# schematic.net
KiCad netlist of a schematic drawn in EAGLE
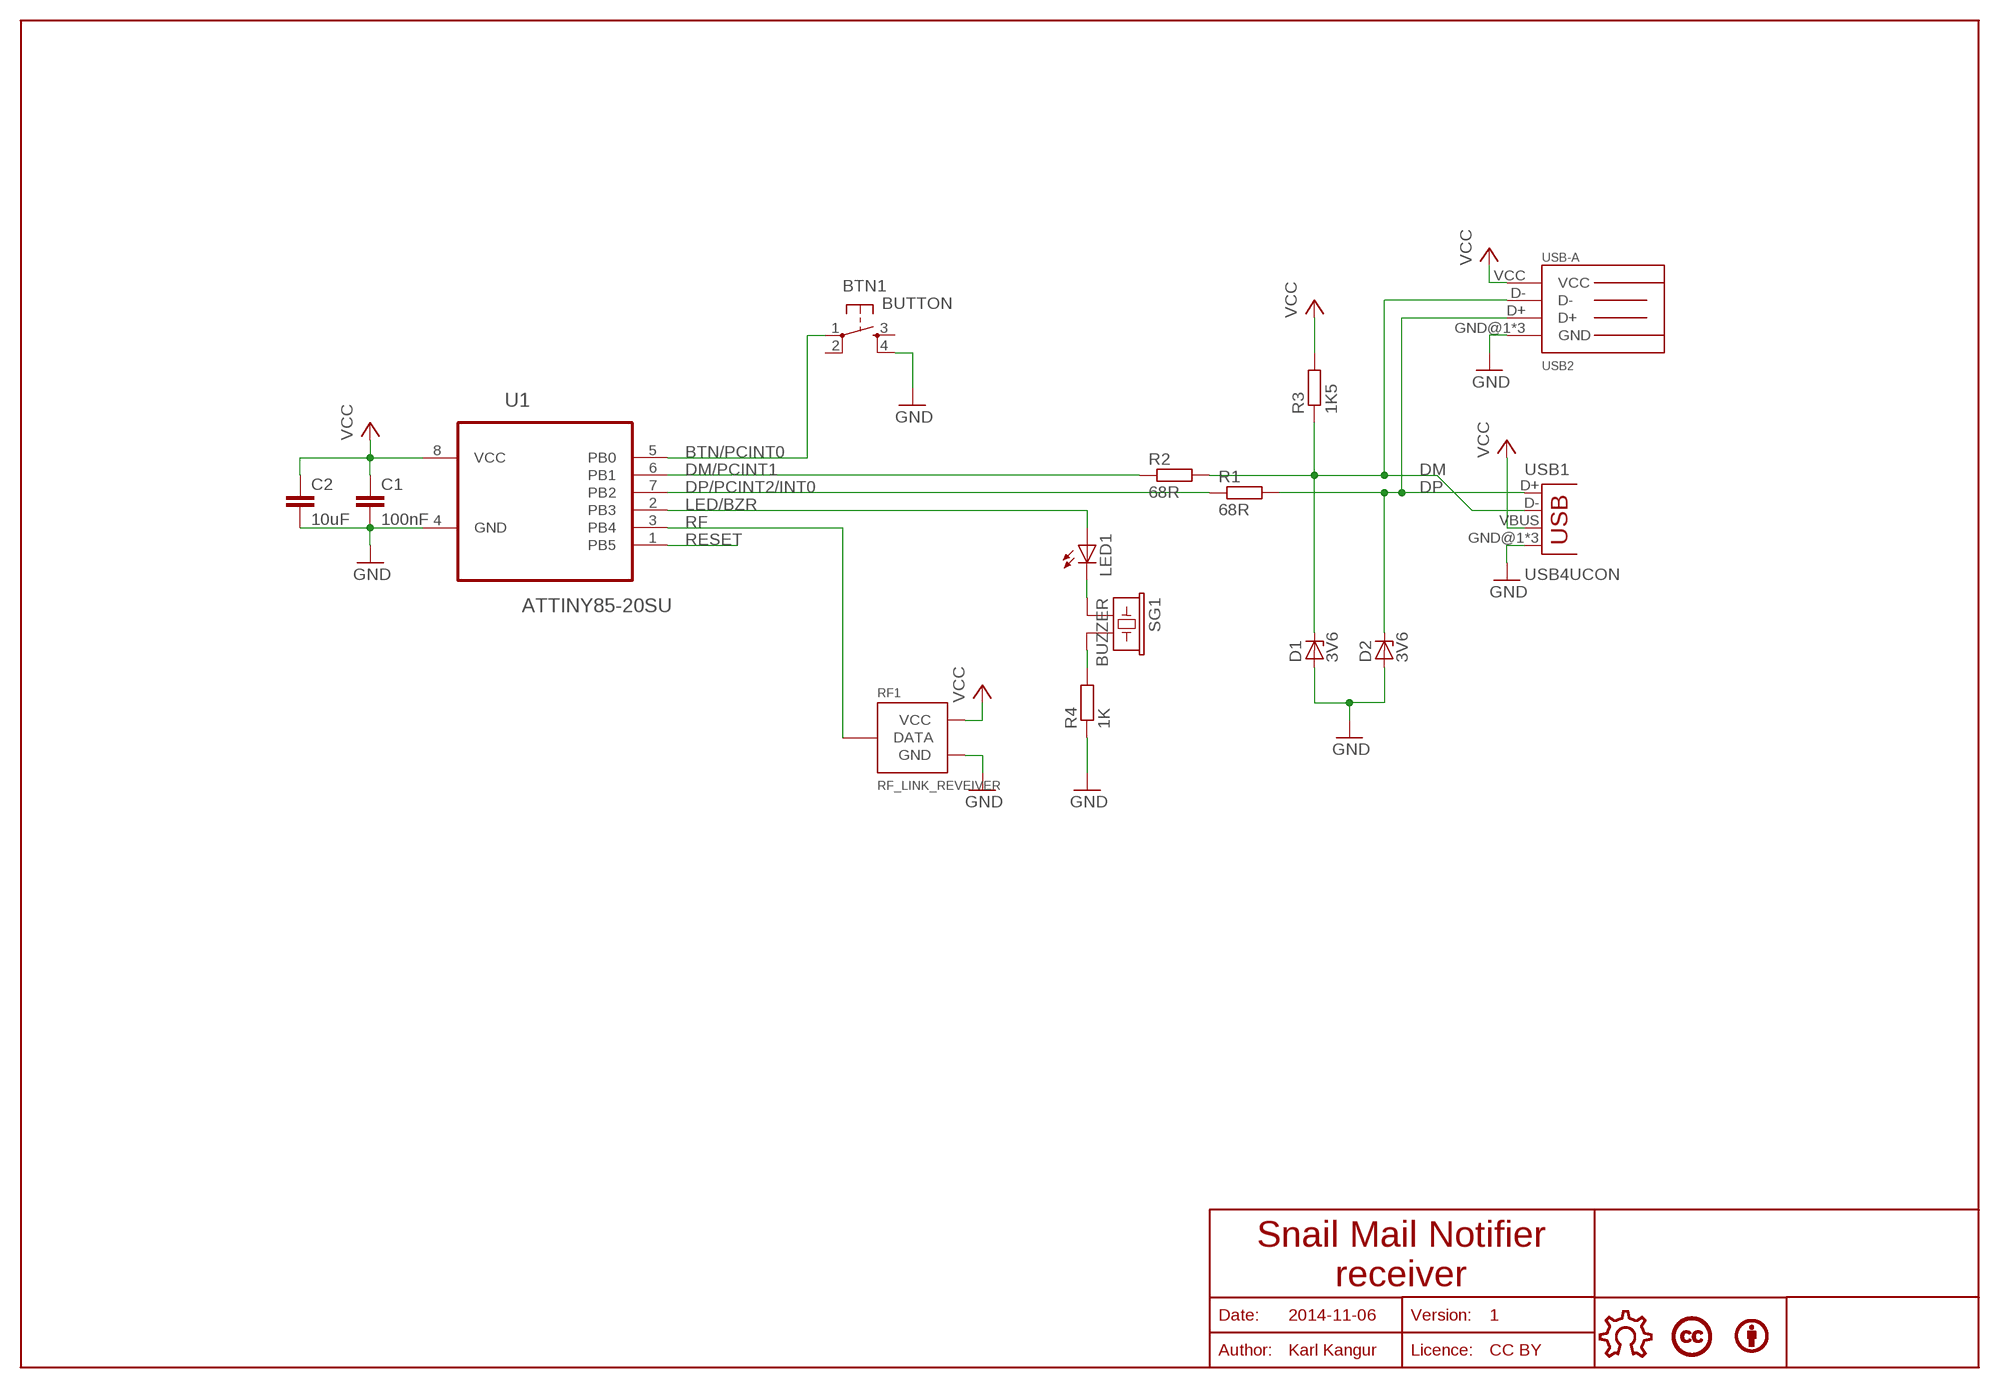
[diagram p0: schematic, sheet 1]

(export (version "E")
  (design (tool "Eeschema 10.0.6"))
  (components
    (comp (ref "BTN1")
      (value "BUTTON")
      (footprint "eagle-import:BUTTON")
      (libsource (lib "eagle-import") (part "BUTTON"))
    )
    (comp (ref "BY1")
      (value "BYBOTTOM")
      (footprint "eagle-import:BY")
      (libsource (lib "eagle-import") (part "BYBOTTOM"))
    )
    (comp (ref "C1")
      (value "100nF")
      (footprint "eagle-import:C0805")
      (libsource (lib "eagle-import") (part "C-EUC0805"))
    )
    (comp (ref "C2")
      (value "10uF")
      (footprint "eagle-import:C0805")
      (libsource (lib "eagle-import") (part "C-EUC0805"))
    )
    (comp (ref "D1")
      (value "3V6")
      (footprint "eagle-import:SOD80C")
      (libsource (lib "eagle-import") (part "ZENER-DIODESOD80C"))
    )
    (comp (ref "D2")
      (value "3V6")
      (footprint "eagle-import:SOD80C")
      (libsource (lib "eagle-import") (part "ZENER-DIODESOD80C"))
    )
    (comp (ref "LED1")
      (value "LEDCHIP-LED0805")
      (footprint "eagle-import:CHIP-LED0805")
      (libsource (lib "eagle-import") (part "LEDCHIP-LED0805"))
    )
    (comp (ref "LICENCE1")
      (value "LICENCECC-BOTTOM")
      (footprint "eagle-import:CREATIVE-COMMONS")
      (libsource (lib "eagle-import") (part "LICENCECC-BOTTOM"))
    )
    (comp (ref "R1")
      (value "68R")
      (footprint "eagle-import:R0805")
      (libsource (lib "eagle-import") (part "R-EU_R0805"))
    )
    (comp (ref "R2")
      (value "68R")
      (footprint "eagle-import:R0805")
      (libsource (lib "eagle-import") (part "R-EU_R0805"))
    )
    (comp (ref "R3")
      (value "1K5")
      (footprint "eagle-import:R0805")
      (libsource (lib "eagle-import") (part "R-EU_R0805"))
    )
    (comp (ref "R4")
      (value "1K")
      (footprint "eagle-import:R0805")
      (libsource (lib "eagle-import") (part "R-EU_R0805"))
    )
    (comp (ref "RF1")
      (value "RF_LINK_REVEIVER")
      (footprint "eagle-import:RF_LINK_REVEIVER")
      (libsource (lib "eagle-import") (part "RF_LINK_REVEIVER"))
    )
    (comp (ref "SG1")
      (value "BUZZER")
      (footprint "eagle-import:PS1240P02BT")
      (libsource (lib "eagle-import") (part "BUZZER"))
    )
    (comp (ref "U$5")
      (value "OPEN-HARDWARE-LOGOBOTTOM-SMALL")
      (footprint "eagle-import:OPEN-HARDWARE-BOTTOM-SMALL")
      (libsource (lib "eagle-import") (part "OPEN-HARDWARE-LOGOBOTTOM-SMALL"))
    )
    (comp (ref "U1")
      (value "ATTINY85-20SU")
      (footprint "eagle-import:SOIC127P798X216-8N")
      (libsource (lib "eagle-import") (part "ATTINY85-20SU"))
    )
    (comp (ref "USB1")
      (value "USB4UCON")
      (footprint "eagle-import:USB-MICROB-4UCON")
      (libsource (lib "eagle-import") (part "USB4UCON"))
    )
    (comp (ref "USB2")
      (value "USB-A")
      (footprint "eagle-import:USB-A")
      (libsource (lib "eagle-import") (part "USB-A"))
    )
  )
  (nets
    (net (code "1") (name "/BTN{slash}PCINT0") (class "Default")
      (node (ref "BTN1") (pin "1") (pinfunction "1_1") (pintype "passive"))
      (node (ref "U1") (pin "5") (pinfunction "PB0_5") (pintype "bidirectional"))
    )
    (net (code "2") (name "/DM") (class "Default")
      (node (ref "D1") (pin "C") (pinfunction "C_C") (pintype "passive"))
      (node (ref "R2") (pin "2") (pinfunction "2_2") (pintype "passive"))
      (node (ref "R3") (pin "1") (pinfunction "1_1") (pintype "passive"))
      (node (ref "USB1") (pin "D-") (pinfunction "D-_D-") (pintype "bidirectional"))
      (node (ref "USB2") (pin "D-") (pinfunction "D-_D-") (pintype "bidirectional"))
    )
    (net (code "3") (name "/DM{slash}PCINT1") (class "Default")
      (node (ref "R2") (pin "1") (pinfunction "1_1") (pintype "passive"))
      (node (ref "U1") (pin "6") (pinfunction "PB1_6") (pintype "bidirectional"))
    )
    (net (code "4") (name "/DP") (class "Default")
      (node (ref "D2") (pin "C") (pinfunction "C_C") (pintype "passive"))
      (node (ref "R1") (pin "2") (pinfunction "2_2") (pintype "passive"))
      (node (ref "USB1") (pin "D+") (pinfunction "D+_D+") (pintype "bidirectional"))
      (node (ref "USB2") (pin "D+") (pinfunction "D+_D+") (pintype "bidirectional"))
    )
    (net (code "5") (name "/DP{slash}PCINT2{slash}INT0") (class "Default")
      (node (ref "R1") (pin "1") (pinfunction "1_1") (pintype "passive"))
      (node (ref "U1") (pin "7") (pinfunction "PB2_7") (pintype "bidirectional"))
    )
    (net (code "6") (name "/LED{slash}BZR") (class "Default")
      (node (ref "LED1") (pin "A") (pinfunction "A_A") (pintype "passive"))
      (node (ref "U1") (pin "2") (pinfunction "PB3_2") (pintype "bidirectional"))
    )
    (net (code "7") (name "/RESET") (class "Default")
      (node (ref "U1") (pin "1") (pinfunction "PB5_1") (pintype "bidirectional"))
    )
    (net (code "8") (name "/RF") (class "Default")
      (node (ref "RF1") (pin "DATA@1") (pinfunction "DATA_DATA@1") (pintype "bidirectional"))
      (node (ref "RF1") (pin "DATA@2") (pinfunction "DATA_DATA@2") (pintype "bidirectional"))
      (node (ref "U1") (pin "3") (pinfunction "PB4_3") (pintype "bidirectional"))
    )
    (net (code "9") (name "GND") (class "Default")
      (node (ref "BTN1") (pin "4") (pinfunction "4_4") (pintype "passive"))
      (node (ref "C1") (pin "2") (pinfunction "2_2") (pintype "passive"))
      (node (ref "C2") (pin "2") (pinfunction "2_2") (pintype "passive"))
      (node (ref "D1") (pin "A") (pinfunction "A_A") (pintype "passive"))
      (node (ref "D2") (pin "A") (pinfunction "A_A") (pintype "passive"))
      (node (ref "R4") (pin "1") (pinfunction "1_1") (pintype "passive"))
      (node (ref "RF1") (pin "GND") (pinfunction "GND_GND") (pintype "bidirectional"))
      (node (ref "U1") (pin "4") (pinfunction "GND_4") (pintype "passive"))
      (node (ref "USB1") (pin "GND@1") (pinfunction "GND_GND@1") (pintype "bidirectional"))
      (node (ref "USB1") (pin "GND@4") (pinfunction "GND_GND@4") (pintype "bidirectional"))
      (node (ref "USB1") (pin "GND@5") (pinfunction "GND_GND@5") (pintype "bidirectional"))
      (node (ref "USB2") (pin "GND@1") (pinfunction "GND_GND@1") (pintype "bidirectional"))
      (node (ref "USB2") (pin "GND@2") (pinfunction "GND_GND@2") (pintype "bidirectional"))
      (node (ref "USB2") (pin "GND@3") (pinfunction "GND_GND@3") (pintype "bidirectional"))
    )
    (net (code "10") (name "Net-(SG1-1)") (class "Default")
      (node (ref "LED1") (pin "C") (pinfunction "C_C") (pintype "passive"))
      (node (ref "SG1") (pin "P$1") (pinfunction "1_P$1") (pintype "passive"))
    )
    (net (code "11") (name "Net-(SG1-2)") (class "Default")
      (node (ref "R4") (pin "2") (pinfunction "2_2") (pintype "passive"))
      (node (ref "SG1") (pin "P$2") (pinfunction "2_P$2") (pintype "passive"))
    )
    (net (code "12") (name "VCC") (class "Default")
      (node (ref "C1") (pin "1") (pinfunction "1_1") (pintype "passive"))
      (node (ref "C2") (pin "1") (pinfunction "1_1") (pintype "passive"))
      (node (ref "R3") (pin "2") (pinfunction "2_2") (pintype "passive"))
      (node (ref "RF1") (pin "VCC") (pinfunction "VCC_VCC") (pintype "bidirectional"))
      (node (ref "U1") (pin "8") (pinfunction "VCC_8") (pintype "power_in"))
      (node (ref "USB1") (pin "VBUS") (pinfunction "VBUS_VBUS") (pintype "bidirectional"))
      (node (ref "USB2") (pin "VCC") (pinfunction "VCC_VCC") (pintype "bidirectional"))
    )
    (net (code "13") (name "unconnected-(BTN1-Pad2)") (class "Default")
      (node (ref "BTN1") (pin "2") (pinfunction "2_2") (pintype "passive"))
    )
    (net (code "14") (name "unconnected-(BTN1-Pad3)") (class "Default")
      (node (ref "BTN1") (pin "3") (pinfunction "3_3") (pintype "passive"))
    )
  )
)
